# Booster.net
KiCad netlist of a schematic drawn in Altium Designer
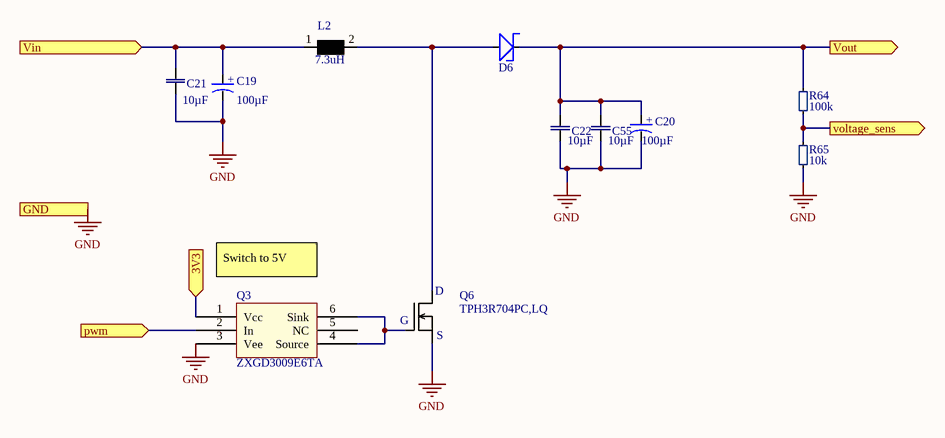
[diagram p0: Booster.SchDoc]

(export (version "E")
  (design (tool "Eeschema 10.0.6"))
  (components
    (comp (ref "C19")
      (value "865080545012")
      (footprint "CAPAE7966X77N")
      (description "Cap Aluminum Lytic 100uF 35V 20% (6.3 X 7.7mm) SMD 300mA 2000h 105C T/R")
      (fields (field (name "CAPACITANCE") "100µF") (field (name "TOLERANCE") "20%"))
      (libsource (lib "concord server") (part "Capasitor_electrolyt_generic"))
    )
    (comp (ref "C20")
      (value "865080545012")
      (footprint "CAPAE7966X77N")
      (description "Cap Aluminum Lytic 100uF 35V 20% (6.3 X 7.7mm) SMD 300mA 2000h 105C T/R")
      (fields (field (name "CAPACITANCE") "100µF") (field (name "TOLERANCE") "20%"))
      (libsource (lib "concord server") (part "Capasitor_electrolyt_generic"))
    )
    (comp (ref "C21")
      (value "CL31A106MBHNNNE")
      (footprint "Chip2PinSM127P600-8N")
      (description "CAP CER 10UF 50V X5R 1206")
      (fields
        (field (name "CAPACITANCE") "10µF")
        (field (name "TOLERANCE") "20%")
        (field (name "LCSC PART#") "C96600")
      )
      (libsource (lib "concord server") (part "Capasitor_keramic_generic"))
    )
    (comp (ref "C22")
      (value "CL31A106MBHNNNE")
      (footprint "Chip2PinSM127P600-8N")
      (description "CAP CER 10UF 50V X5R 1206")
      (fields
        (field (name "CAPACITANCE") "10µF")
        (field (name "TOLERANCE") "20%")
        (field (name "LCSC PART#") "C96600")
      )
      (libsource (lib "concord server") (part "Capasitor_keramic_generic"))
    )
    (comp (ref "C55")
      (value "CL31A106MBHNNNE")
      (footprint "Chip2PinSM127P600-8N")
      (description "CAP CER 10UF 50V X5R 1206")
      (fields
        (field (name "CAPACITANCE") "10µF")
        (field (name "TOLERANCE") "20%")
        (field (name "LCSC PART#") "C96600")
      )
      (libsource (lib "concord server") (part "Capasitor_keramic_generic"))
    )
    (comp (ref "D6")
      (value "MBR12100LPS-TP")
      (footprint "DFN445P552X120-3N")
      (description "Diode Schottky 100V 12A TO277B")
      (libsource (lib "concord server") (part "Schootkey diode"))
    )
    (comp (ref "L2")
      (value "7443551730")
      (footprint "INDP130128X65N")
      (fields
        (field (name "INDUCTANCE") "7.3uH")
        (field (name "TOLERANCE") "20%")
        (field (name "LCSC PART#") "C1331154")
      )
      (libsource (lib "concord server") (part "Inductor"))
    )
    (comp (ref "Q3")
      (value "ZXGD3009E6TA")
      (footprint "SOT95P285X110-6N")
      (description "IC GATE DRVR IGBT/MOSFET SOT23-6")
      (fields (field (name "LCSC PART#") "C156293"))
      (libsource (lib "concord server") (part "ZXGD3009E6TA-Symbol-1"))
    )
    (comp (ref "Q6")
      (value "TPH3R704PC,LQ")
      (footprint "TPH3R704PC,LQ-Footprint-1")
      (description "MOSFET N-Channel Enhancement Mode 40V 8-Pin SOP")
      (libsource (lib "concord server") (part "nmos"))
    )
    (comp (ref "R64")
      (value "RC0402FR-07100KL")
      (footprint "SMD_0402(1005)_M")
      (description "Res General Purpose Thick Film 0402 100K Ohm 1% 1/16W ±100ppm/°C Molded SMD Paper T/R")
      (fields
        (field (name "RESISTANCE") "100k")
        (field (name "TOLERANCE") "1%")
        (field (name "LCSC PART#") "C60491")
      )
      (libsource (lib "concord server") (part "resistor_european"))
    )
    (comp (ref "R65")
      (value "RC0402FR-0710KL")
      (footprint "SMD_0402(1005)_M")
      (description "Surface Mount Thick Film Resistor, Rc Series, 10 Kohm, 62.5 Mw, - 1%, 50 V, 0402 [1005 Metric]")
      (fields
        (field (name "RESISTANCE") "10k")
        (field (name "TOLERANCE") "1%")
        (field (name "LCSC PART#") "C60490")
      )
      (libsource (lib "concord server") (part "resistor_european"))
    )
  )
  (nets
    (net (code "1") (name "/3V3") (class "Default")
      (node (ref "Q3") (pin "1") (pinfunction "Vcc_1") (pintype "passive"))
    )
    (net (code "2") (name "/Vin") (class "Default")
      (node (ref "C19") (pin "1") (pinfunction "+_1") (pintype "passive"))
      (node (ref "C21") (pin "2") (pinfunction "2_2") (pintype "passive"))
      (node (ref "L2") (pin "1") (pintype "passive"))
    )
    (net (code "3") (name "/Vout") (class "Default")
      (node (ref "C20") (pin "1") (pinfunction "+_1") (pintype "passive"))
      (node (ref "C22") (pin "2") (pinfunction "2_2") (pintype "passive"))
      (node (ref "C55") (pin "2") (pinfunction "2_2") (pintype "passive"))
      (node (ref "D6") (pin "1") (pinfunction "K_1") (pintype "passive"))
      (node (ref "R64") (pin "2") (pinfunction "2_2") (pintype "passive"))
    )
    (net (code "4") (name "/pwm") (class "Default")
      (node (ref "Q3") (pin "2") (pinfunction "In_2") (pintype "passive"))
    )
    (net (code "5") (name "/voltage_sens") (class "Default")
      (node (ref "R64") (pin "1") (pinfunction "1_1") (pintype "passive"))
      (node (ref "R65") (pin "2") (pinfunction "2_2") (pintype "passive"))
    )
    (net (code "6") (name "GND") (class "Default")
      (node (ref "C19") (pin "2") (pinfunction "-_2") (pintype "passive"))
      (node (ref "C20") (pin "2") (pinfunction "-_2") (pintype "passive"))
      (node (ref "C21") (pin "1") (pinfunction "1_1") (pintype "passive"))
      (node (ref "C22") (pin "1") (pinfunction "1_1") (pintype "passive"))
      (node (ref "C55") (pin "1") (pinfunction "1_1") (pintype "passive"))
      (node (ref "Q3") (pin "3") (pinfunction "Vee_3") (pintype "passive"))
      (node (ref "Q6") (pin "1") (pinfunction "D_1") (pintype "passive"))
      (node (ref "R65") (pin "1") (pinfunction "1_1") (pintype "passive"))
    )
    (net (code "7") (name "Net-(D6-A)") (class "Default")
      (node (ref "D6") (pin "2") (pinfunction "A_2") (pintype "passive"))
      (node (ref "L2") (pin "2") (pintype "passive"))
      (node (ref "Q6") (pin "2") (pinfunction "S_2") (pintype "passive"))
    )
    (net (code "8") (name "Net-(Q3-Sink)") (class "Default")
      (node (ref "Q3") (pin "4") (pinfunction "Source_4") (pintype "passive"))
      (node (ref "Q3") (pin "6") (pinfunction "Sink_6") (pintype "passive"))
      (node (ref "Q6") (pin "3") (pinfunction "G_3") (pintype "passive"))
    )
    (net (code "9") (name "unconnected-(Q3-NC-Pad5)") (class "Default")
      (node (ref "Q3") (pin "5") (pinfunction "NC_5") (pintype "passive"))
    )
  )
)
